# MB.net
KiCad netlist of a schematic drawn in EAGLE
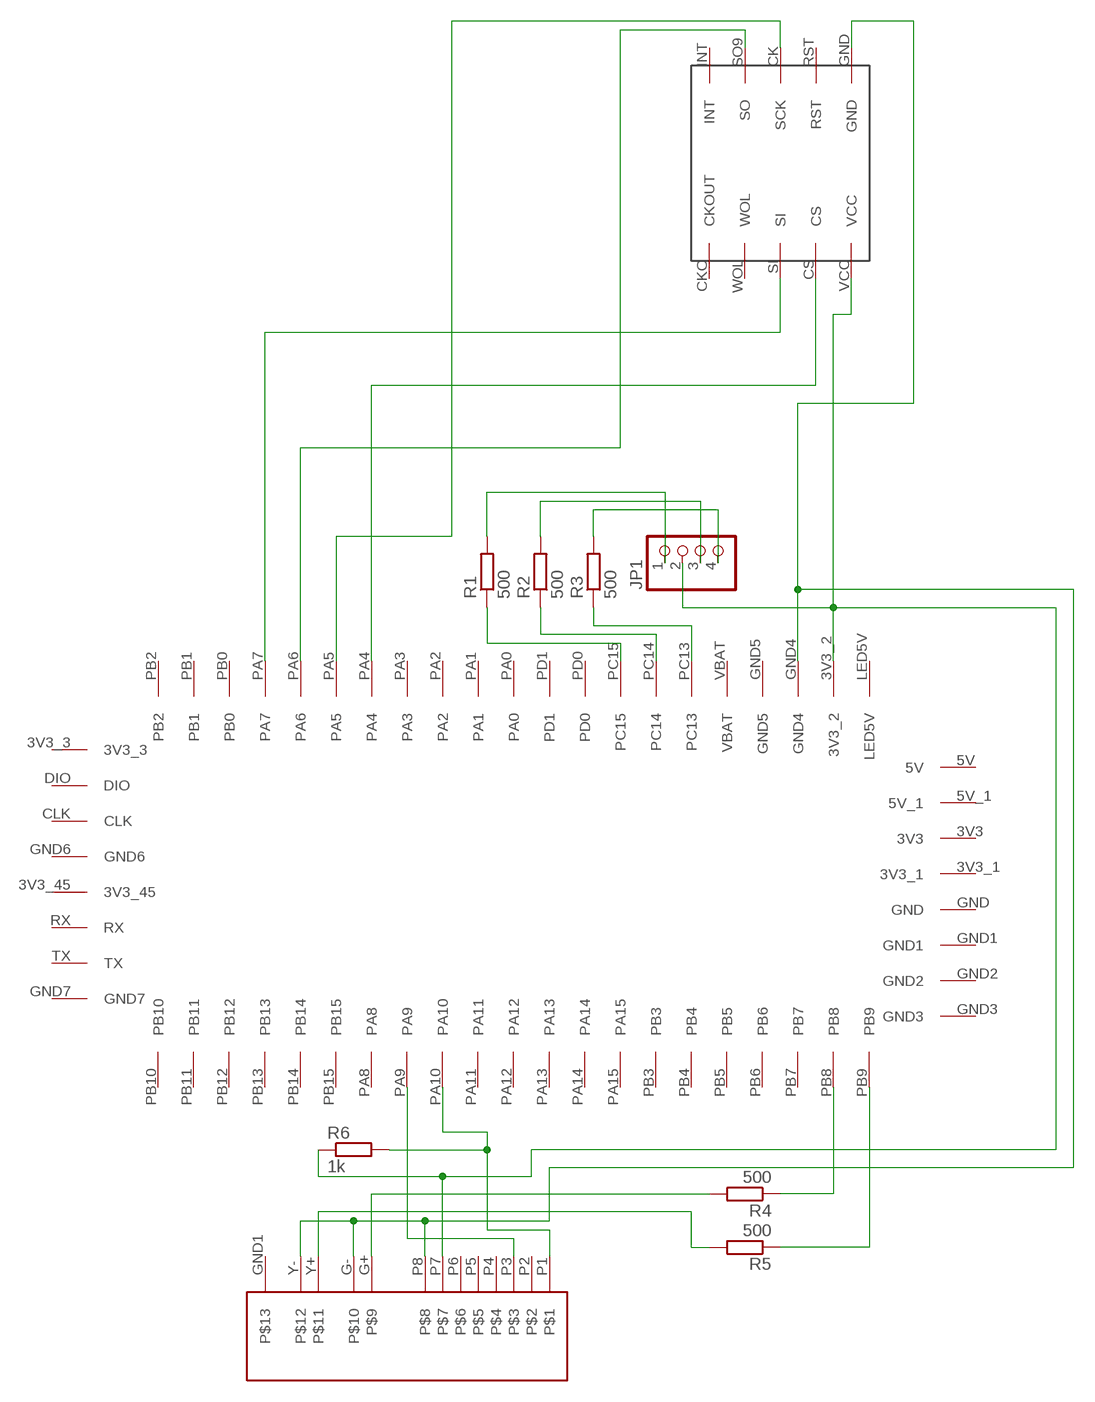
[diagram p0: schematic, sheet 1]

(export (version "E")
  (design (tool "Eeschema 10.0.6"))
  (components
    (comp (ref "JP1")
      (value "PINHD-1X4")
      (footprint "eagle-import:1X04")
      (libsource (lib "eagle-import") (part "PINHD-1X4"))
    )
    (comp (ref "R1")
      (value "500")
      (footprint "eagle-import:M1206")
      (libsource (lib "eagle-import") (part "R-EU_M1206"))
    )
    (comp (ref "R2")
      (value "500")
      (footprint "eagle-import:M1206")
      (libsource (lib "eagle-import") (part "R-EU_M1206"))
    )
    (comp (ref "R3")
      (value "500")
      (footprint "eagle-import:M1206")
      (libsource (lib "eagle-import") (part "R-EU_M1206"))
    )
    (comp (ref "R4")
      (value "500")
      (footprint "eagle-import:M1206")
      (libsource (lib "eagle-import") (part "R-EU_M1206"))
    )
    (comp (ref "R5")
      (value "500")
      (footprint "eagle-import:M1206")
      (libsource (lib "eagle-import") (part "R-EU_M1206"))
    )
    (comp (ref "R6")
      (value "1k")
      (footprint "eagle-import:M1206")
      (libsource (lib "eagle-import") (part "R-EU_M1206"))
    )
    (comp (ref "U$1")
      (value "F100X_SYSBOARD")
      (footprint "eagle-import:F10X_SYSBOARD")
      (libsource (lib "eagle-import") (part "F100X_SYSBOARD"))
    )
    (comp (ref "U$2")
      (value "SPI_ETHERNET")
      (footprint "eagle-import:SPI_ETHERNET")
      (libsource (lib "eagle-import") (part "SPI_ETHERNET"))
    )
    (comp (ref "U$3")
      (value "RJ-45_LEDS")
      (footprint "eagle-import:RJ-45_LEDS")
      (libsource (lib "eagle-import") (part "RJ-45_LEDS"))
    )
  )
  (nets
    (net (code "1") (name "/3V3") (class "Default")
      (node (ref "U$1") (pin "3V3") (pinfunction "3V3_3V3") (pintype "power_in"))
    )
    (net (code "2") (name "/3V3_1") (class "Default")
      (node (ref "U$1") (pin "3V3_1") (pinfunction "3V3_1_3V3_1") (pintype "power_in"))
    )
    (net (code "3") (name "/5V") (class "Default")
      (node (ref "U$1") (pin "5V") (pinfunction "5V_5V") (pintype "power_in"))
    )
    (net (code "4") (name "/5V_1") (class "Default")
      (node (ref "U$1") (pin "5V_1") (pinfunction "5V_1_5V_1") (pintype "power_in"))
    )
    (net (code "5") (name "/GND") (class "Default")
      (node (ref "U$1") (pin "GND") (pinfunction "GND_GND") (pintype "power_in"))
    )
    (net (code "6") (name "/GND1") (class "Default")
      (node (ref "U$1") (pin "GND1") (pinfunction "GND1_GND1") (pintype "power_in"))
    )
    (net (code "7") (name "/GND5") (class "Default")
      (node (ref "U$1") (pin "GND5") (pinfunction "GND5_GND5") (pintype "power_in"))
    )
    (net (code "8") (name "/LED5V") (class "Default")
      (node (ref "U$1") (pin "LED5V") (pinfunction "LED5V_LED5V") (pintype "power_in"))
    )
    (net (code "9") (name "/P$13") (class "Default")
      (node (ref "U$3") (pin "GND1") (pinfunction "P$13_GND1") (pintype "power_in"))
    )
    (net (code "10") (name "/VBAT") (class "Default")
      (node (ref "U$1") (pin "VBAT") (pinfunction "VBAT_VBAT") (pintype "power_in"))
    )
    (net (code "11") (name "Net-(JP1-Pad1)") (class "Default")
      (node (ref "JP1") (pin "1") (pinfunction "1_1") (pintype "passive"))
      (node (ref "R1") (pin "2") (pinfunction "2_2") (pintype "passive"))
    )
    (net (code "12") (name "Net-(JP1-Pad3)") (class "Default")
      (node (ref "JP1") (pin "3") (pinfunction "3_3") (pintype "passive"))
      (node (ref "R2") (pin "2") (pinfunction "2_2") (pintype "passive"))
    )
    (net (code "13") (name "Net-(JP1-Pad4)") (class "Default")
      (node (ref "JP1") (pin "4") (pinfunction "4_4") (pintype "passive"))
      (node (ref "R3") (pin "2") (pinfunction "2_2") (pintype "passive"))
    )
    (net (code "14") (name "Net-(R1-Pad1)") (class "Default")
      (node (ref "R1") (pin "1") (pinfunction "1_1") (pintype "passive"))
      (node (ref "U$1") (pin "PC15") (pinfunction "PC15_PC15") (pintype "bidirectional"))
    )
    (net (code "15") (name "Net-(R2-Pad1)") (class "Default")
      (node (ref "R2") (pin "1") (pinfunction "1_1") (pintype "passive"))
      (node (ref "U$1") (pin "PC14") (pinfunction "PC14_PC14") (pintype "bidirectional"))
    )
    (net (code "16") (name "Net-(R3-Pad1)") (class "Default")
      (node (ref "R3") (pin "1") (pinfunction "1_1") (pintype "passive"))
      (node (ref "U$1") (pin "PC13") (pinfunction "PC13_PC13") (pintype "bidirectional"))
    )
    (net (code "17") (name "Net-(R4-Pad1)") (class "Default")
      (node (ref "R4") (pin "1") (pinfunction "1_1") (pintype "passive"))
      (node (ref "U$1") (pin "PB8") (pinfunction "PB8_PB8") (pintype "bidirectional"))
    )
    (net (code "18") (name "Net-(R5-Pad1)") (class "Default")
      (node (ref "R5") (pin "1") (pinfunction "1_1") (pintype "passive"))
      (node (ref "U$1") (pin "PB9") (pinfunction "PB9_PB9") (pintype "bidirectional"))
    )
    (net (code "19") (name "Net-(U$1-PadPA4)") (class "Default")
      (node (ref "U$1") (pin "PA4") (pinfunction "PA4_PA4") (pintype "bidirectional"))
      (node (ref "U$2") (pin "CS") (pinfunction "CS_CS") (pintype "bidirectional"))
    )
    (net (code "20") (name "Net-(U$1-PadPA7)") (class "Default")
      (node (ref "U$1") (pin "PA7") (pinfunction "PA7_PA7") (pintype "bidirectional"))
      (node (ref "U$2") (pin "SI") (pinfunction "SI_SI") (pintype "bidirectional"))
    )
    (net (code "21") (name "Net-(U$2-SCK)") (class "Default")
      (node (ref "U$1") (pin "PA5") (pinfunction "PA5_PA5") (pintype "bidirectional"))
      (node (ref "U$2") (pin "CK") (pinfunction "SCK_CK") (pintype "bidirectional"))
    )
    (net (code "22") (name "Net-(U$2-SO)") (class "Default")
      (node (ref "U$1") (pin "PA6") (pinfunction "PA6_PA6") (pintype "bidirectional"))
      (node (ref "U$2") (pin "SO9") (pinfunction "SO_SO9") (pintype "bidirectional"))
    )
    (net (code "23") (name "Net-(U$3-P$1)") (class "Default")
      (node (ref "R6") (pin "2") (pinfunction "2_2") (pintype "passive"))
      (node (ref "U$1") (pin "PA10") (pinfunction "PA10_PA10") (pintype "bidirectional"))
      (node (ref "U$3") (pin "P1") (pinfunction "P$1_P1") (pintype "bidirectional"))
    )
    (net (code "24") (name "Net-(U$3-P$3)") (class "Default")
      (node (ref "U$1") (pin "PA9") (pinfunction "PA9_PA9") (pintype "bidirectional"))
      (node (ref "U$3") (pin "P3") (pinfunction "P$3_P3") (pintype "bidirectional"))
    )
    (net (code "25") (name "Net-(U$3-P$7)") (class "Default")
      (node (ref "JP1") (pin "2") (pinfunction "2_2") (pintype "passive"))
      (node (ref "R6") (pin "1") (pinfunction "1_1") (pintype "passive"))
      (node (ref "U$1") (pin "3V3_2") (pinfunction "3V3_2_3V3_2") (pintype "power_in"))
      (node (ref "U$2") (pin "VCC") (pinfunction "VCC_VCC") (pintype "power_in"))
      (node (ref "U$3") (pin "P7") (pinfunction "P$7_P7") (pintype "bidirectional"))
    )
    (net (code "26") (name "Net-(U$3-P$9)") (class "Default")
      (node (ref "R4") (pin "2") (pinfunction "2_2") (pintype "passive"))
      (node (ref "U$3") (pin "G+") (pinfunction "P$9_G+") (pintype "power_in"))
    )
    (net (code "27") (name "Net-(U$3-P$10)") (class "Default")
      (node (ref "U$1") (pin "GND4") (pinfunction "GND4_GND4") (pintype "power_in"))
      (node (ref "U$2") (pin "GND") (pinfunction "GND_GND") (pintype "power_in"))
      (node (ref "U$3") (pin "G-") (pinfunction "P$10_G-") (pintype "power_in"))
      (node (ref "U$3") (pin "P8") (pinfunction "P$8_P8") (pintype "bidirectional"))
      (node (ref "U$3") (pin "Y-") (pinfunction "P$12_Y-") (pintype "power_in"))
    )
    (net (code "28") (name "Net-(U$3-P$11)") (class "Default")
      (node (ref "R5") (pin "2") (pinfunction "2_2") (pintype "passive"))
      (node (ref "U$3") (pin "Y+") (pinfunction "P$11_Y+") (pintype "power_in"))
    )
    (net (code "29") (name "unconnected-(U$1-Pad3V3_3)") (class "Default")
      (node (ref "U$1") (pin "3V3_3") (pinfunction "3V3_3_3V3_3") (pintype "bidirectional"))
    )
    (net (code "30") (name "unconnected-(U$1-Pad3V3_45)") (class "Default")
      (node (ref "U$1") (pin "3V3_45") (pinfunction "3V3_45_3V3_45") (pintype "bidirectional"))
    )
    (net (code "31") (name "unconnected-(U$1-PadCLK)") (class "Default")
      (node (ref "U$1") (pin "CLK") (pinfunction "CLK_CLK") (pintype "bidirectional"))
    )
    (net (code "32") (name "unconnected-(U$1-PadDIO)") (class "Default")
      (node (ref "U$1") (pin "DIO") (pinfunction "DIO_DIO") (pintype "bidirectional"))
    )
    (net (code "33") (name "unconnected-(U$1-PadGND2)") (class "Default")
      (node (ref "U$1") (pin "GND2") (pinfunction "GND2_GND2") (pintype "bidirectional"))
    )
    (net (code "34") (name "unconnected-(U$1-PadGND3)") (class "Default")
      (node (ref "U$1") (pin "GND3") (pinfunction "GND3_GND3") (pintype "bidirectional"))
    )
    (net (code "35") (name "unconnected-(U$1-PadGND6)") (class "Default")
      (node (ref "U$1") (pin "GND6") (pinfunction "GND6_GND6") (pintype "bidirectional"))
    )
    (net (code "36") (name "unconnected-(U$1-PadGND7)") (class "Default")
      (node (ref "U$1") (pin "GND7") (pinfunction "GND7_GND7") (pintype "bidirectional"))
    )
    (net (code "37") (name "unconnected-(U$1-PadPA0)") (class "Default")
      (node (ref "U$1") (pin "PA0") (pinfunction "PA0_PA0") (pintype "bidirectional"))
    )
    (net (code "38") (name "unconnected-(U$1-PadPA1)") (class "Default")
      (node (ref "U$1") (pin "PA1") (pinfunction "PA1_PA1") (pintype "bidirectional"))
    )
    (net (code "39") (name "unconnected-(U$1-PadPA2)") (class "Default")
      (node (ref "U$1") (pin "PA2") (pinfunction "PA2_PA2") (pintype "bidirectional"))
    )
    (net (code "40") (name "unconnected-(U$1-PadPA3)") (class "Default")
      (node (ref "U$1") (pin "PA3") (pinfunction "PA3_PA3") (pintype "bidirectional"))
    )
    (net (code "41") (name "unconnected-(U$1-PadPA8)") (class "Default")
      (node (ref "U$1") (pin "PA8") (pinfunction "PA8_PA8") (pintype "bidirectional"))
    )
    (net (code "42") (name "unconnected-(U$1-PadPA11)") (class "Default")
      (node (ref "U$1") (pin "PA11") (pinfunction "PA11_PA11") (pintype "bidirectional"))
    )
    (net (code "43") (name "unconnected-(U$1-PadPA12)") (class "Default")
      (node (ref "U$1") (pin "PA12") (pinfunction "PA12_PA12") (pintype "bidirectional"))
    )
    (net (code "44") (name "unconnected-(U$1-PadPA13)") (class "Default")
      (node (ref "U$1") (pin "PA13") (pinfunction "PA13_PA13") (pintype "bidirectional"))
    )
    (net (code "45") (name "unconnected-(U$1-PadPA14)") (class "Default")
      (node (ref "U$1") (pin "PA14") (pinfunction "PA14_PA14") (pintype "bidirectional"))
    )
    (net (code "46") (name "unconnected-(U$1-PadPA15)") (class "Default")
      (node (ref "U$1") (pin "PA15") (pinfunction "PA15_PA15") (pintype "bidirectional"))
    )
    (net (code "47") (name "unconnected-(U$1-PadPB0)") (class "Default")
      (node (ref "U$1") (pin "PB0") (pinfunction "PB0_PB0") (pintype "bidirectional"))
    )
    (net (code "48") (name "unconnected-(U$1-PadPB1)") (class "Default")
      (node (ref "U$1") (pin "PB1") (pinfunction "PB1_PB1") (pintype "bidirectional"))
    )
    (net (code "49") (name "unconnected-(U$1-PadPB2)") (class "Default")
      (node (ref "U$1") (pin "PB2") (pinfunction "PB2_PB2") (pintype "bidirectional"))
    )
    (net (code "50") (name "unconnected-(U$1-PadPB3)") (class "Default")
      (node (ref "U$1") (pin "PB3") (pinfunction "PB3_PB3") (pintype "bidirectional"))
    )
    (net (code "51") (name "unconnected-(U$1-PadPB4)") (class "Default")
      (node (ref "U$1") (pin "PB4") (pinfunction "PB4_PB4") (pintype "bidirectional"))
    )
    (net (code "52") (name "unconnected-(U$1-PadPB5)") (class "Default")
      (node (ref "U$1") (pin "PB5") (pinfunction "PB5_PB5") (pintype "bidirectional"))
    )
    (net (code "53") (name "unconnected-(U$1-PadPB6)") (class "Default")
      (node (ref "U$1") (pin "PB6") (pinfunction "PB6_PB6") (pintype "bidirectional"))
    )
    (net (code "54") (name "unconnected-(U$1-PadPB7)") (class "Default")
      (node (ref "U$1") (pin "PB7") (pinfunction "PB7_PB7") (pintype "bidirectional"))
    )
    (net (code "55") (name "unconnected-(U$1-PadPB10)") (class "Default")
      (node (ref "U$1") (pin "PB10") (pinfunction "PB10_PB10") (pintype "bidirectional"))
    )
    (net (code "56") (name "unconnected-(U$1-PadPB11)") (class "Default")
      (node (ref "U$1") (pin "PB11") (pinfunction "PB11_PB11") (pintype "bidirectional"))
    )
    (net (code "57") (name "unconnected-(U$1-PadPB12)") (class "Default")
      (node (ref "U$1") (pin "PB12") (pinfunction "PB12_PB12") (pintype "bidirectional"))
    )
    (net (code "58") (name "unconnected-(U$1-PadPB13)") (class "Default")
      (node (ref "U$1") (pin "PB13") (pinfunction "PB13_PB13") (pintype "bidirectional"))
    )
    (net (code "59") (name "unconnected-(U$1-PadPB14)") (class "Default")
      (node (ref "U$1") (pin "PB14") (pinfunction "PB14_PB14") (pintype "bidirectional"))
    )
    (net (code "60") (name "unconnected-(U$1-PadPB15)") (class "Default")
      (node (ref "U$1") (pin "PB15") (pinfunction "PB15_PB15") (pintype "bidirectional"))
    )
    (net (code "61") (name "unconnected-(U$1-PadPD0)") (class "Default")
      (node (ref "U$1") (pin "PD0") (pinfunction "PD0_PD0") (pintype "bidirectional"))
    )
    (net (code "62") (name "unconnected-(U$1-PadPD1)") (class "Default")
      (node (ref "U$1") (pin "PD1") (pinfunction "PD1_PD1") (pintype "bidirectional"))
    )
    (net (code "63") (name "unconnected-(U$1-PadRX)") (class "Default")
      (node (ref "U$1") (pin "RX") (pinfunction "RX_RX") (pintype "bidirectional"))
    )
    (net (code "64") (name "unconnected-(U$1-PadTX)") (class "Default")
      (node (ref "U$1") (pin "TX") (pinfunction "TX_TX") (pintype "bidirectional"))
    )
    (net (code "65") (name "unconnected-(U$2-CKOUT-PadCKO)") (class "Default")
      (node (ref "U$2") (pin "CKO") (pinfunction "CKOUT_CKO") (pintype "bidirectional"))
    )
    (net (code "66") (name "unconnected-(U$2-PadINT)") (class "Default")
      (node (ref "U$2") (pin "INT") (pinfunction "INT_INT") (pintype "bidirectional"))
    )
    (net (code "67") (name "unconnected-(U$2-PadRST)") (class "Default")
      (node (ref "U$2") (pin "RST") (pinfunction "RST_RST") (pintype "bidirectional"))
    )
    (net (code "68") (name "unconnected-(U$2-PadWOL)") (class "Default")
      (node (ref "U$2") (pin "WOL") (pinfunction "WOL_WOL") (pintype "bidirectional"))
    )
    (net (code "69") (name "unconnected-(U$3-P$2-PadP2)") (class "Default")
      (node (ref "U$3") (pin "P2") (pinfunction "P$2_P2") (pintype "bidirectional"))
    )
    (net (code "70") (name "unconnected-(U$3-P$4-PadP4)") (class "Default")
      (node (ref "U$3") (pin "P4") (pinfunction "P$4_P4") (pintype "bidirectional"))
    )
    (net (code "71") (name "unconnected-(U$3-P$5-PadP5)") (class "Default")
      (node (ref "U$3") (pin "P5") (pinfunction "P$5_P5") (pintype "bidirectional"))
    )
    (net (code "72") (name "unconnected-(U$3-P$6-PadP6)") (class "Default")
      (node (ref "U$3") (pin "P6") (pinfunction "P$6_P6") (pintype "bidirectional"))
    )
  )
)
